# clock_controller.net
KiCad netlist of a schematic drawn in Altium Designer
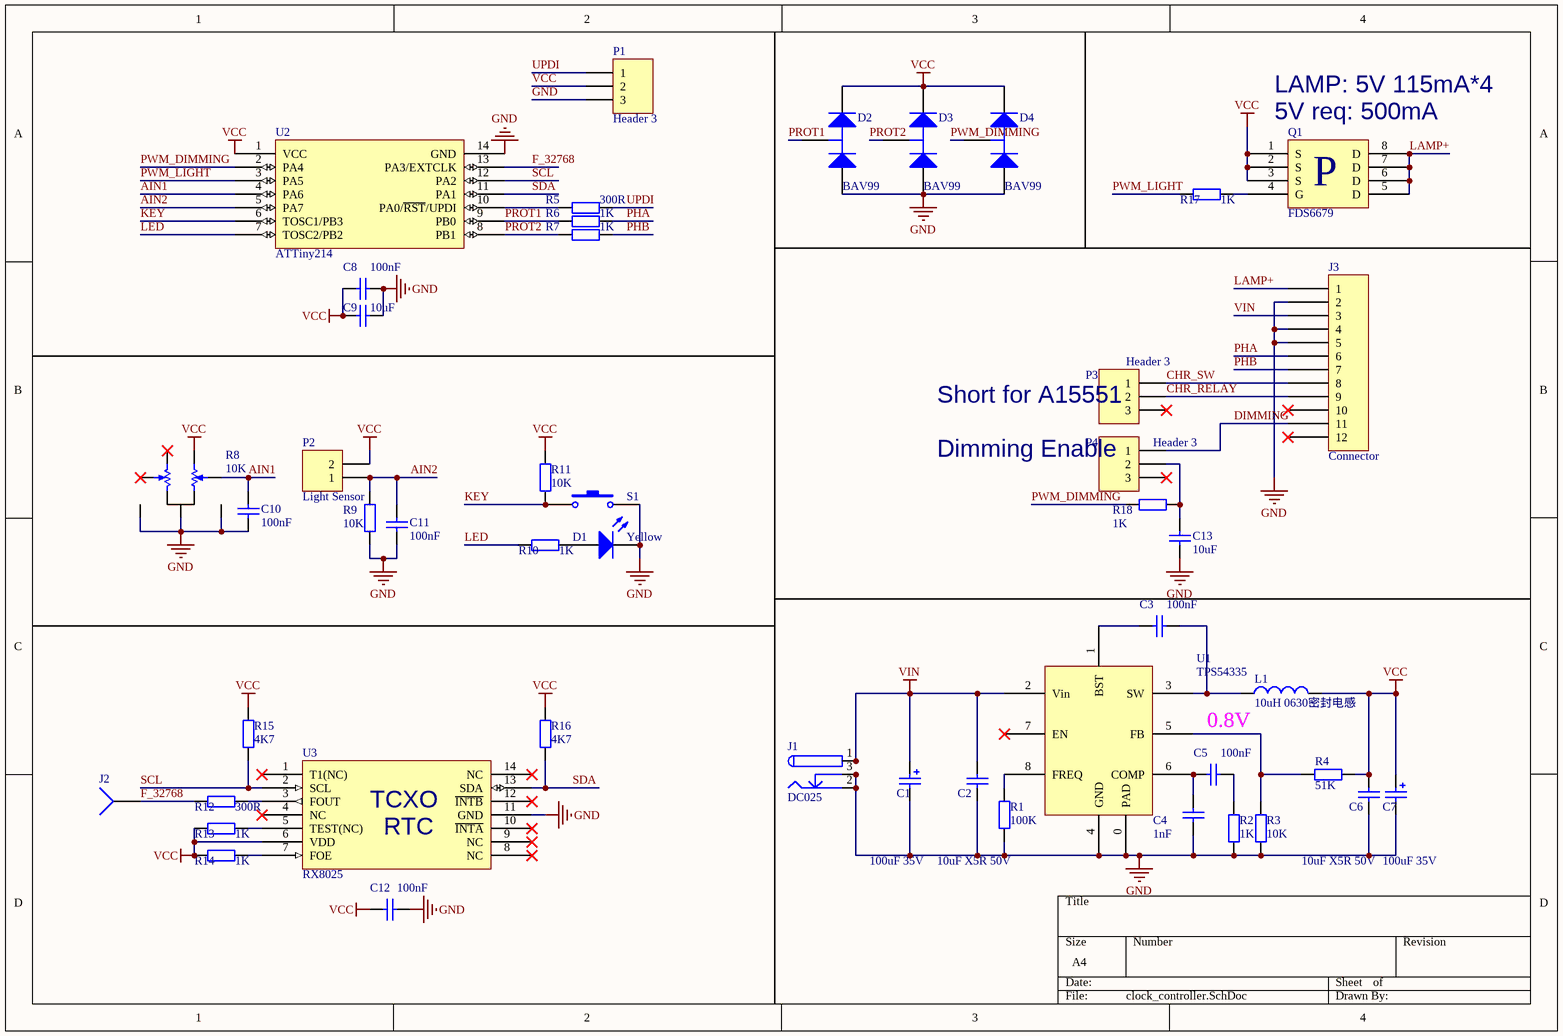
[diagram p0: clock_controller.SchDoc]

(export (version "E")
  (design (tool "Eeschema 10.0.6"))
  (components
    (comp (ref "C1")
      (value "100uF 35V")
      (footprint "C6380POL")
      (description "Polarized Capacitor (Axial)")
      (fields (field (name "PUBLISHER") "Altium Limited"))
      (libsource (lib "Miscellaneous Devices") (part "Cap Pol2"))
    )
    (comp (ref "C2")
      (value "10uF X5R 50V")
      (footprint "C1206")
      (description "Capacitor")
      (fields (field (name "PUBLISHER") "Altium Limited"))
      (libsource (lib "Miscellaneous Devices") (part "Cap"))
    )
    (comp (ref "C3")
      (value "100nF")
      (footprint "C0603")
      (description "Capacitor")
      (fields (field (name "PUBLISHER") "Altium Limited"))
      (libsource (lib "Miscellaneous Devices") (part "Cap"))
    )
    (comp (ref "C4")
      (value "1nF")
      (footprint "C0603")
      (description "Capacitor")
      (fields (field (name "PUBLISHER") "Altium Limited"))
      (libsource (lib "Miscellaneous Devices") (part "Cap"))
    )
    (comp (ref "C5")
      (value "100nF")
      (footprint "C0603")
      (description "Capacitor")
      (fields (field (name "PUBLISHER") "Altium Limited"))
      (libsource (lib "Miscellaneous Devices") (part "Cap"))
    )
    (comp (ref "C6")
      (value "10uF X5R 50V")
      (footprint "C1206")
      (description "Capacitor")
      (fields (field (name "PUBLISHER") "Altium Limited"))
      (libsource (lib "Miscellaneous Devices") (part "Cap"))
    )
    (comp (ref "C7")
      (value "100uF 35V")
      (footprint "C6380POL")
      (description "Polarized Capacitor (Axial)")
      (fields (field (name "PUBLISHER") "Altium Limited"))
      (libsource (lib "Miscellaneous Devices") (part "Cap Pol2"))
    )
    (comp (ref "C8")
      (value "100nF")
      (footprint "C0603")
      (description "Capacitor")
      (fields (field (name "PUBLISHER") "Altium Limited"))
      (libsource (lib "Miscellaneous Devices") (part "Cap"))
    )
    (comp (ref "C9")
      (value "10uF")
      (footprint "C1206")
      (description "Capacitor")
      (fields (field (name "PUBLISHER") "Altium Limited"))
      (libsource (lib "Miscellaneous Devices") (part "Cap"))
    )
    (comp (ref "C10")
      (value "100nF")
      (footprint "C0603")
      (description "Capacitor")
      (fields (field (name "PUBLISHER") "Altium Limited"))
      (libsource (lib "Miscellaneous Devices") (part "Cap"))
    )
    (comp (ref "C11")
      (value "100nF")
      (footprint "C0603")
      (description "Capacitor")
      (fields (field (name "PUBLISHER") "Altium Limited"))
      (libsource (lib "Miscellaneous Devices") (part "Cap"))
    )
    (comp (ref "C12")
      (value "100nF")
      (footprint "C0603")
      (description "Capacitor")
      (fields (field (name "PUBLISHER") "Altium Limited"))
      (libsource (lib "Miscellaneous Devices") (part "Cap"))
    )
    (comp (ref "C13")
      (value "10uF")
      (footprint "C1206")
      (description "Capacitor")
      (fields (field (name "PUBLISHER") "Altium Limited"))
      (libsource (lib "Miscellaneous Devices") (part "Cap"))
    )
    (comp (ref "D1")
      (value "Yellow")
      (footprint "LED0805")
      (description "Typical INFRARED GaAs LED")
      (fields (field (name "PUBLISHER") "Altium Limited"))
      (libsource (lib "CenterController") (part "LED0"))
    )
    (comp (ref "D2")
      (value "BAV99")
      (footprint "SOT23")
      (description "SOT23 Silicon Planar High-Speed Switching Series Diode Pair")
      (fields (field (name "PUBLISHER") "Altium Limited"))
      (libsource (lib "CenterController") (part "BAV99"))
    )
    (comp (ref "D3")
      (value "BAV99")
      (footprint "SOT23")
      (description "SOT23 Silicon Planar High-Speed Switching Series Diode Pair")
      (fields (field (name "PUBLISHER") "Altium Limited"))
      (libsource (lib "CenterController") (part "BAV99"))
    )
    (comp (ref "D4")
      (value "BAV99")
      (footprint "SOT23")
      (description "SOT23 Silicon Planar High-Speed Switching Series Diode Pair")
      (fields (field (name "PUBLISHER") "Altium Limited"))
      (libsource (lib "CenterController") (part "BAV99"))
    )
    (comp (ref "J1")
      (value "DC025")
      (footprint "DC025M")
      (description "CON,PWR2.5 DC025M 2.1mm芯")
      (libsource (lib "clock_controller") (part "DC025"))
    )
    (comp (ref "J2")
      (value "Socket")
      (footprint "PIN1")
      (fields (field (name "PUBLISHER") "Altium Limited"))
      (libsource (lib "Miscellaneous Connectors") (part "Socket"))
    )
    (comp (ref "J3")
      (value "Connector")
      (footprint "MS27034H12B12PN")
      (libsource (lib "clock_controller") (part "CON_MS27034H12B12PN"))
    )
    (comp (ref "L1")
      (value "10uH 0630密封电感")
      (footprint "Inductor0630")
      (description "Inductor")
      (fields (field (name "PUBLISHER") "Altium Limited"))
      (libsource (lib "Miscellaneous Devices") (part "Inductor"))
    )
    (comp (ref "P1")
      (value "Header 3")
      (footprint "HDR1X3")
      (description "Header, 3-Pin")
      (fields (field (name "PUBLISHER") "Altium Limited"))
      (libsource (lib "") (part "Header 3_1"))
    )
    (comp (ref "P2")
      (value "Light Sensor")
      (footprint "HDR1X2")
      (description "Header, 2-Pin")
      (fields (field (name "PUBLISHER") "Altium Limited"))
      (libsource (lib "Miscellaneous Connectors") (part "Header 2"))
    )
    (comp (ref "P3")
      (value "Header 3")
      (footprint "HDR1X3")
      (description "Header, 3-Pin")
      (fields (field (name "PUBLISHER") "Altium Limited"))
      (libsource (lib "Miscellaneous Connectors") (part "Header 3"))
    )
    (comp (ref "P4")
      (value "Header 3")
      (footprint "HDR1X3")
      (description "Header, 3-Pin")
      (fields (field (name "PUBLISHER") "Altium Limited"))
      (libsource (lib "Miscellaneous Connectors") (part "Header 3"))
    )
    (comp (ref "Q1")
      (value "FDS6679")
      (footprint "SO-8")
      (libsource (lib "LHF's SCH Library") (part "FDS6679"))
    )
    (comp (ref "R1")
      (value "100K")
      (footprint "R0603")
      (description "Resistor")
      (fields (field (name "PUBLISHER") "Altium Limited"))
      (libsource (lib "") (part "Res2_2"))
    )
    (comp (ref "R2")
      (value "1K")
      (footprint "R0603")
      (description "Resistor")
      (fields (field (name "PUBLISHER") "Altium Limited"))
      (libsource (lib "") (part "Res2_2"))
    )
    (comp (ref "R3")
      (value "10K")
      (footprint "R0603")
      (description "Resistor")
      (fields (field (name "PUBLISHER") "Altium Limited"))
      (libsource (lib "") (part "Res2_2"))
    )
    (comp (ref "R4")
      (value "51K")
      (footprint "R0603")
      (description "Resistor")
      (fields (field (name "PUBLISHER") "Altium Limited"))
      (libsource (lib "Miscellaneous Devices") (part "Res2"))
    )
    (comp (ref "R5")
      (value "300R")
      (footprint "R0603")
      (description "Resistor")
      (fields (field (name "PUBLISHER") "Altium Limited"))
      (libsource (lib "") (part "Res2_1"))
    )
    (comp (ref "R6")
      (value "1K")
      (footprint "R0603")
      (description "Resistor")
      (fields (field (name "PUBLISHER") "Altium Limited"))
      (libsource (lib "") (part "Res2_1"))
    )
    (comp (ref "R7")
      (value "1K")
      (footprint "R0603")
      (description "Resistor")
      (fields (field (name "PUBLISHER") "Altium Limited"))
      (libsource (lib "") (part "Res2_1"))
    )
    (comp (ref "R8")
      (value "10K")
      (footprint "RK10J")
      (description "Square Trimming Potentiometer")
      (fields (field (name "PUBLISHER") "Altium Limited"))
      (libsource (lib "clock_controller") (part "RK10J"))
    )
    (comp (ref "R9")
      (value "10K")
      (footprint "R0603")
      (description "Resistor")
      (fields (field (name "PUBLISHER") "Altium Limited"))
      (libsource (lib "") (part "Res2_3"))
    )
    (comp (ref "R10")
      (value "1K")
      (footprint "R0603")
      (description "Resistor")
      (fields (field (name "PUBLISHER") "Altium Limited"))
      (libsource (lib "") (part "Res2_1"))
    )
    (comp (ref "R11")
      (value "10K")
      (footprint "R0603")
      (description "Resistor")
      (fields (field (name "PUBLISHER") "Altium Limited"))
      (libsource (lib "") (part "Res2_2"))
    )
    (comp (ref "R12")
      (value "300R")
      (footprint "R0603")
      (description "Resistor")
      (fields (field (name "PUBLISHER") "Altium Limited"))
      (libsource (lib "") (part "Res2_1"))
    )
    (comp (ref "R13")
      (value "1K")
      (footprint "R0603")
      (description "Resistor")
      (fields (field (name "PUBLISHER") "Altium Limited"))
      (libsource (lib "") (part "Res2_1"))
    )
    (comp (ref "R14")
      (value "1K")
      (footprint "R0603")
      (description "Resistor")
      (fields (field (name "PUBLISHER") "Altium Limited"))
      (libsource (lib "") (part "Res2_1"))
    )
    (comp (ref "R15")
      (value "4K7")
      (footprint "R0603")
      (description "Resistor")
      (fields (field (name "PUBLISHER") "Altium Limited"))
      (libsource (lib "") (part "Res2_2"))
    )
    (comp (ref "R16")
      (value "4K7")
      (footprint "R0603")
      (description "Resistor")
      (fields (field (name "PUBLISHER") "Altium Limited"))
      (libsource (lib "") (part "Res2_2"))
    )
    (comp (ref "R17")
      (value "1K")
      (footprint "R0603")
      (description "Resistor")
      (fields (field (name "PUBLISHER") "Altium Limited"))
      (libsource (lib "") (part "Res2_1"))
    )
    (comp (ref "R18")
      (value "1K")
      (footprint "R0603")
      (description "Resistor")
      (fields (field (name "PUBLISHER") "Altium Limited"))
      (libsource (lib "Miscellaneous Devices") (part "Res2"))
    )
    (comp (ref "S1")
      (value "SW-PB")
      (footprint "BUTTON_SMT")
      (description "Switch")
      (fields (field (name "PUBLISHER") "Altium Limited"))
      (libsource (lib "Miscellaneous Devices") (part "SW-PB"))
    )
    (comp (ref "U1")
      (value "TPS54335")
      (footprint "SO-8-Thermal")
      (libsource (lib "clock_controller") (part "TPS54335"))
    )
    (comp (ref "U2")
      (value "ATTiny214")
      (footprint "SO-14")
      (libsource (lib "clock_controller") (part "ATTiny214"))
    )
    (comp (ref "U3")
      (value "RX8025")
      (footprint "SO-14")
      (libsource (lib "clock_controller") (part "RX8025T"))
    )
  )
  (nets
    (net (code "1") (name "/AIN1") (class "Default")
      (node (ref "C10") (pin "2") (pinfunction "2_2") (pintype "passive"))
      (node (ref "R8") (pin "3") (pinfunction "3_3") (pintype "passive"))
      (node (ref "U2") (pin "4") (pinfunction "PA6_4") (pintype "bidirectional"))
    )
    (net (code "2") (name "/AIN2") (class "Default")
      (node (ref "C11") (pin "2") (pinfunction "2_2") (pintype "passive"))
      (node (ref "P2") (pin "1") (pinfunction "1_1") (pintype "passive"))
      (node (ref "R9") (pin "2") (pinfunction "2_2") (pintype "passive"))
      (node (ref "U2") (pin "5") (pinfunction "PA7_5") (pintype "bidirectional"))
    )
    (net (code "3") (name "/CHR_RELAY") (class "Default")
      (node (ref "J3") (pin "9") (pinfunction "9_9") (pintype "passive"))
      (node (ref "P3") (pin "2") (pinfunction "2_2") (pintype "passive"))
    )
    (net (code "4") (name "/CHR_SW") (class "Default")
      (node (ref "J3") (pin "8") (pinfunction "8_8") (pintype "passive"))
      (node (ref "P3") (pin "1") (pinfunction "1_1") (pintype "passive"))
    )
    (net (code "5") (name "/DIMMING") (class "Default")
      (node (ref "J3") (pin "11") (pinfunction "11_11") (pintype "passive"))
      (node (ref "P4") (pin "1") (pinfunction "1_1") (pintype "passive"))
    )
    (net (code "6") (name "/F_32768") (class "Default")
      (node (ref "J2") (pin "1") (pinfunction "1_1") (pintype "passive"))
      (node (ref "R12") (pin "2") (pinfunction "2_2") (pintype "passive"))
      (node (ref "U2") (pin "13") (pinfunction "PA3/EXTCLK_13") (pintype "bidirectional"))
    )
    (net (code "7") (name "/KEY") (class "Default")
      (node (ref "R11") (pin "2") (pinfunction "2_2") (pintype "passive"))
      (node (ref "S1") (pin "1") (pinfunction "1_1") (pintype "passive"))
      (node (ref "U2") (pin "6") (pinfunction "TOSC1/PB3_6") (pintype "bidirectional"))
    )
    (net (code "8") (name "/LAMP+") (class "Default")
      (node (ref "J3") (pin "1") (pinfunction "1_1") (pintype "passive"))
      (node (ref "Q1") (pin "5") (pinfunction "D_5") (pintype "passive"))
      (node (ref "Q1") (pin "6") (pinfunction "D_6") (pintype "passive"))
      (node (ref "Q1") (pin "7") (pinfunction "D_7") (pintype "passive"))
      (node (ref "Q1") (pin "8") (pinfunction "D_8") (pintype "passive"))
    )
    (net (code "9") (name "/LED") (class "Default")
      (node (ref "R10") (pin "2") (pinfunction "2_2") (pintype "passive"))
      (node (ref "U2") (pin "7") (pinfunction "TOSC2/PB2_7") (pintype "bidirectional"))
    )
    (net (code "10") (name "/PHA") (class "Default")
      (node (ref "J3") (pin "6") (pinfunction "6_6") (pintype "passive"))
      (node (ref "R6") (pin "1") (pinfunction "1_1") (pintype "passive"))
    )
    (net (code "11") (name "/PHB") (class "Default")
      (node (ref "J3") (pin "7") (pinfunction "7_7") (pintype "passive"))
      (node (ref "R7") (pin "1") (pinfunction "1_1") (pintype "passive"))
    )
    (net (code "12") (name "/PROT1") (class "Default")
      (node (ref "D2") (pin "1") (pinfunction "C_1") (pintype "passive"))
      (node (ref "R6") (pin "2") (pinfunction "2_2") (pintype "passive"))
      (node (ref "U2") (pin "9") (pinfunction "PB0_9") (pintype "bidirectional"))
    )
    (net (code "13") (name "/PROT2") (class "Default")
      (node (ref "D3") (pin "1") (pinfunction "C_1") (pintype "passive"))
      (node (ref "R7") (pin "2") (pinfunction "2_2") (pintype "passive"))
      (node (ref "U2") (pin "8") (pinfunction "PB1_8") (pintype "bidirectional"))
    )
    (net (code "14") (name "/PWM_DIMMING") (class "Default")
      (node (ref "D4") (pin "1") (pinfunction "C_1") (pintype "passive"))
      (node (ref "R18") (pin "1") (pinfunction "1_1") (pintype "passive"))
      (node (ref "U2") (pin "2") (pinfunction "PA4_2") (pintype "bidirectional"))
    )
    (net (code "15") (name "/PWM_LIGHT") (class "Default")
      (node (ref "R17") (pin "2") (pinfunction "2_2") (pintype "passive"))
      (node (ref "U2") (pin "3") (pinfunction "PA5_3") (pintype "bidirectional"))
    )
    (net (code "16") (name "/SCL") (class "Default")
      (node (ref "R15") (pin "2") (pinfunction "2_2") (pintype "passive"))
      (node (ref "U2") (pin "12") (pinfunction "PA2_12") (pintype "bidirectional"))
      (node (ref "U3") (pin "2") (pinfunction "SCL_2") (pintype "input"))
    )
    (net (code "17") (name "/SDA") (class "Default")
      (node (ref "R16") (pin "2") (pinfunction "2_2") (pintype "passive"))
      (node (ref "U2") (pin "11") (pinfunction "PA1_11") (pintype "bidirectional"))
      (node (ref "U3") (pin "13") (pinfunction "SDA_13") (pintype "bidirectional"))
    )
    (net (code "18") (name "/UPDI") (class "Default")
      (node (ref "P1") (pin "1") (pinfunction "1_1") (pintype "passive"))
      (node (ref "R5") (pin "1") (pinfunction "1_1") (pintype "passive"))
    )
    (net (code "19") (name "GND") (class "Default")
      (node (ref "C1") (pin "2") (pinfunction "2_2") (pintype "passive"))
      (node (ref "C10") (pin "1") (pinfunction "1_1") (pintype "passive"))
      (node (ref "C11") (pin "1") (pinfunction "1_1") (pintype "passive"))
      (node (ref "C12") (pin "2") (pinfunction "2_2") (pintype "passive"))
      (node (ref "C13") (pin "1") (pinfunction "1_1") (pintype "passive"))
      (node (ref "C2") (pin "1") (pinfunction "1_1") (pintype "passive"))
      (node (ref "C4") (pin "1") (pinfunction "1_1") (pintype "passive"))
      (node (ref "C6") (pin "1") (pinfunction "1_1") (pintype "passive"))
      (node (ref "C7") (pin "2") (pinfunction "2_2") (pintype "passive"))
      (node (ref "C8") (pin "2") (pinfunction "2_2") (pintype "passive"))
      (node (ref "C9") (pin "2") (pinfunction "2_2") (pintype "passive"))
      (node (ref "D1") (pin "2") (pinfunction "K_2") (pintype "passive"))
      (node (ref "D2") (pin "3") (pinfunction "A_3") (pintype "passive"))
      (node (ref "D3") (pin "3") (pinfunction "A_3") (pintype "passive"))
      (node (ref "D4") (pin "3") (pinfunction "A_3") (pintype "passive"))
      (node (ref "J1") (pin "2") (pinfunction "2_2") (pintype "power_in"))
      (node (ref "J1") (pin "2A") (pinfunction "2A_2A") (pintype "power_in"))
      (node (ref "J1") (pin "2B") (pinfunction "2B_2B") (pintype "power_in"))
      (node (ref "J1") (pin "3") (pinfunction "3_3") (pintype "power_in"))
      (node (ref "J1") (pin "3A") (pinfunction "3A_3A") (pintype "power_in"))
      (node (ref "J1") (pin "3B") (pinfunction "3B_3B") (pintype "power_in"))
      (node (ref "J3") (pin "2") (pinfunction "2_2") (pintype "passive"))
      (node (ref "J3") (pin "4") (pinfunction "4_4") (pintype "passive"))
      (node (ref "J3") (pin "5") (pinfunction "5_5") (pintype "passive"))
      (node (ref "P1") (pin "3") (pinfunction "3_3") (pintype "passive"))
      (node (ref "R1") (pin "2") (pinfunction "2_2") (pintype "passive"))
      (node (ref "R2") (pin "2") (pinfunction "2_2") (pintype "passive"))
      (node (ref "R3") (pin "2") (pinfunction "2_2") (pintype "passive"))
      (node (ref "R8") (pin "1") (pinfunction "-_1") (pintype "passive"))
      (node (ref "R8") (pin "6") (pinfunction "-_6") (pintype "passive"))
      (node (ref "R8") (pin "7") (pinfunction "-_7") (pintype "passive"))
      (node (ref "R9") (pin "1") (pinfunction "1_1") (pintype "passive"))
      (node (ref "S1") (pin "2") (pinfunction "2_2") (pintype "passive"))
      (node (ref "U1") (pin "0") (pinfunction "PAD_0") (pintype "passive"))
      (node (ref "U1") (pin "4") (pinfunction "GND_4") (pintype "passive"))
      (node (ref "U2") (pin "14") (pinfunction "GND_14") (pintype "power_in"))
      (node (ref "U3") (pin "11") (pinfunction "GND_11") (pintype "power_in"))
    )
    (net (code "20") (name "Net-(C5-Pad2)") (class "Default")
      (node (ref "C5") (pin "2") (pinfunction "2_2") (pintype "passive"))
      (node (ref "R2") (pin "1") (pinfunction "1_1") (pintype "passive"))
    )
    (net (code "21") (name "Net-(C13-Pad2)") (class "Default")
      (node (ref "C13") (pin "2") (pinfunction "2_2") (pintype "passive"))
      (node (ref "P4") (pin "2") (pinfunction "2_2") (pintype "passive"))
      (node (ref "R18") (pin "2") (pinfunction "2_2") (pintype "passive"))
    )
    (net (code "22") (name "Net-(D1-A)") (class "Default")
      (node (ref "D1") (pin "1") (pinfunction "A_1") (pintype "passive"))
      (node (ref "R10") (pin "1") (pinfunction "1_1") (pintype "passive"))
    )
    (net (code "23") (name "Net-(Q1-G)") (class "Default")
      (node (ref "Q1") (pin "4") (pinfunction "G_4") (pintype "passive"))
      (node (ref "R17") (pin "1") (pinfunction "1_1") (pintype "passive"))
    )
    (net (code "24") (name "Net-(U1-BST)") (class "Default")
      (node (ref "C3") (pin "1") (pinfunction "1_1") (pintype "passive"))
      (node (ref "U1") (pin "1") (pinfunction "BST_1") (pintype "passive"))
    )
    (net (code "25") (name "Net-(U1-COMP)") (class "Default")
      (node (ref "C4") (pin "2") (pinfunction "2_2") (pintype "passive"))
      (node (ref "C5") (pin "1") (pinfunction "1_1") (pintype "passive"))
      (node (ref "U1") (pin "6") (pinfunction "COMP_6") (pintype "passive"))
    )
    (net (code "26") (name "Net-(U1-FB)") (class "Default")
      (node (ref "R3") (pin "1") (pinfunction "1_1") (pintype "passive"))
      (node (ref "R4") (pin "1") (pinfunction "1_1") (pintype "passive"))
      (node (ref "U1") (pin "5") (pinfunction "FB_5") (pintype "passive"))
    )
    (net (code "27") (name "Net-(U1-FREQ)") (class "Default")
      (node (ref "R1") (pin "1") (pinfunction "1_1") (pintype "passive"))
      (node (ref "U1") (pin "8") (pinfunction "FREQ_8") (pintype "passive"))
    )
    (net (code "28") (name "Net-(U1-SW)") (class "Default")
      (node (ref "C3") (pin "2") (pinfunction "2_2") (pintype "passive"))
      (node (ref "L1") (pin "1") (pinfunction "1_1") (pintype "passive"))
      (node (ref "U1") (pin "3") (pinfunction "SW_3") (pintype "passive"))
    )
    (net (code "29") (name "Net-(U2-PA0{slash}~{RST}{slash}UPDI)") (class "Default")
      (node (ref "R5") (pin "2") (pinfunction "2_2") (pintype "passive"))
      (node (ref "U2") (pin "10") (pinfunction "PA0/~{RST}/UPDI_10") (pintype "bidirectional"))
    )
    (net (code "30") (name "Net-(U3-FOE)") (class "Default")
      (node (ref "R14") (pin "1") (pinfunction "1_1") (pintype "passive"))
      (node (ref "U3") (pin "7") (pinfunction "FOE_7") (pintype "input"))
    )
    (net (code "31") (name "Net-(U3-FOUT)") (class "Default")
      (node (ref "R12") (pin "1") (pinfunction "1_1") (pintype "passive"))
      (node (ref "U3") (pin "3") (pinfunction "FOUT_3") (pintype "output"))
    )
    (net (code "32") (name "Net-(U3-TEST(NC))") (class "Default")
      (node (ref "R13") (pin "1") (pinfunction "1_1") (pintype "passive"))
      (node (ref "U3") (pin "5") (pinfunction "TEST(NC)_5") (pintype "passive"))
    )
    (net (code "33") (name "VCC") (class "Default")
      (node (ref "C12") (pin "1") (pinfunction "1_1") (pintype "passive"))
      (node (ref "C6") (pin "2") (pinfunction "2_2") (pintype "passive"))
      (node (ref "C7") (pin "1") (pinfunction "1_1") (pintype "passive"))
      (node (ref "C8") (pin "1") (pinfunction "1_1") (pintype "passive"))
      (node (ref "C9") (pin "1") (pinfunction "1_1") (pintype "passive"))
      (node (ref "D2") (pin "2") (pinfunction "K_2") (pintype "passive"))
      (node (ref "D3") (pin "2") (pinfunction "K_2") (pintype "passive"))
      (node (ref "D4") (pin "2") (pinfunction "K_2") (pintype "passive"))
      (node (ref "L1") (pin "2") (pinfunction "2_2") (pintype "passive"))
      (node (ref "P1") (pin "2") (pinfunction "2_2") (pintype "passive"))
      (node (ref "P2") (pin "2") (pinfunction "2_2") (pintype "passive"))
      (node (ref "Q1") (pin "1") (pinfunction "S_1") (pintype "passive"))
      (node (ref "Q1") (pin "2") (pinfunction "S_2") (pintype "passive"))
      (node (ref "Q1") (pin "3") (pinfunction "S_3") (pintype "passive"))
      (node (ref "R11") (pin "1") (pinfunction "1_1") (pintype "passive"))
      (node (ref "R13") (pin "2") (pinfunction "2_2") (pintype "passive"))
      (node (ref "R14") (pin "2") (pinfunction "2_2") (pintype "passive"))
      (node (ref "R15") (pin "1") (pinfunction "1_1") (pintype "passive"))
      (node (ref "R16") (pin "1") (pinfunction "1_1") (pintype "passive"))
      (node (ref "R4") (pin "2") (pinfunction "2_2") (pintype "passive"))
      (node (ref "R8") (pin "4") (pinfunction "4_4") (pintype "passive"))
      (node (ref "U2") (pin "1") (pinfunction "VCC_1") (pintype "power_in"))
      (node (ref "U3") (pin "6") (pinfunction "VDD_6") (pintype "power_in"))
    )
    (net (code "34") (name "VIN") (class "Default")
      (node (ref "C1") (pin "1") (pinfunction "1_1") (pintype "passive"))
      (node (ref "C2") (pin "2") (pinfunction "2_2") (pintype "passive"))
      (node (ref "J1") (pin "1") (pinfunction "1_1") (pintype "power_in"))
      (node (ref "J1") (pin "1A") (pinfunction "1A_1A") (pintype "power_in"))
      (node (ref "J1") (pin "1B") (pinfunction "1B_1B") (pintype "power_in"))
      (node (ref "J3") (pin "3") (pinfunction "3_3") (pintype "passive"))
      (node (ref "U1") (pin "2") (pinfunction "Vin_2") (pintype "passive"))
    )
    (net (code "35") (name "unconnected-(J3-Pad10)") (class "Default")
      (node (ref "J3") (pin "10") (pinfunction "10_10") (pintype "passive+no_connect"))
    )
    (net (code "36") (name "unconnected-(J3-Pad12)") (class "Default")
      (node (ref "J3") (pin "12") (pinfunction "12_12") (pintype "passive+no_connect"))
    )
    (net (code "37") (name "unconnected-(P3-Pad3)") (class "Default")
      (node (ref "P3") (pin "3") (pinfunction "3_3") (pintype "passive+no_connect"))
    )
    (net (code "38") (name "unconnected-(P4-Pad3)") (class "Default")
      (node (ref "P4") (pin "3") (pinfunction "3_3") (pintype "passive+no_connect"))
    )
    (net (code "39") (name "unconnected-(R8-Pad2)") (class "Default")
      (node (ref "R8") (pin "2") (pinfunction "2_2") (pintype "passive+no_connect"))
    )
    (net (code "40") (name "unconnected-(R8-Pad5)") (class "Default")
      (node (ref "R8") (pin "5") (pinfunction "5_5") (pintype "passive+no_connect"))
    )
    (net (code "41") (name "unconnected-(U1-EN-Pad7)") (class "Default")
      (node (ref "U1") (pin "7") (pinfunction "EN_7") (pintype "passive+no_connect"))
    )
    (net (code "42") (name "unconnected-(U3-NC-Pad4)") (class "Default")
      (node (ref "U3") (pin "4") (pinfunction "NC_4") (pintype "passive+no_connect"))
    )
    (net (code "43") (name "unconnected-(U3-NC-Pad8)") (class "Default")
      (node (ref "U3") (pin "8") (pinfunction "NC_8") (pintype "passive+no_connect"))
    )
    (net (code "44") (name "unconnected-(U3-NC-Pad9)") (class "Default")
      (node (ref "U3") (pin "9") (pinfunction "NC_9") (pintype "passive+no_connect"))
    )
    (net (code "45") (name "unconnected-(U3-NC-Pad14)") (class "Default")
      (node (ref "U3") (pin "14") (pinfunction "NC_14") (pintype "passive+no_connect"))
    )
    (net (code "46") (name "unconnected-(U3-T1(NC)-Pad1)") (class "Default")
      (node (ref "U3") (pin "1") (pinfunction "T1(NC)_1") (pintype "passive+no_connect"))
    )
    (net (code "47") (name "unconnected-(U3-~{INTA}-Pad10)") (class "Default")
      (node (ref "U3") (pin "10") (pinfunction "~{INTA}_10") (pintype "open_collector+no_connect"))
    )
    (net (code "48") (name "unconnected-(U3-~{INTB}-Pad12)") (class "Default")
      (node (ref "U3") (pin "12") (pinfunction "~{INTB}_12") (pintype "open_collector+no_connect"))
    )
  )
)
